# Enclosure_100x68_PBC-AW2.net
KiCad netlist of a schematic drawn in EAGLE
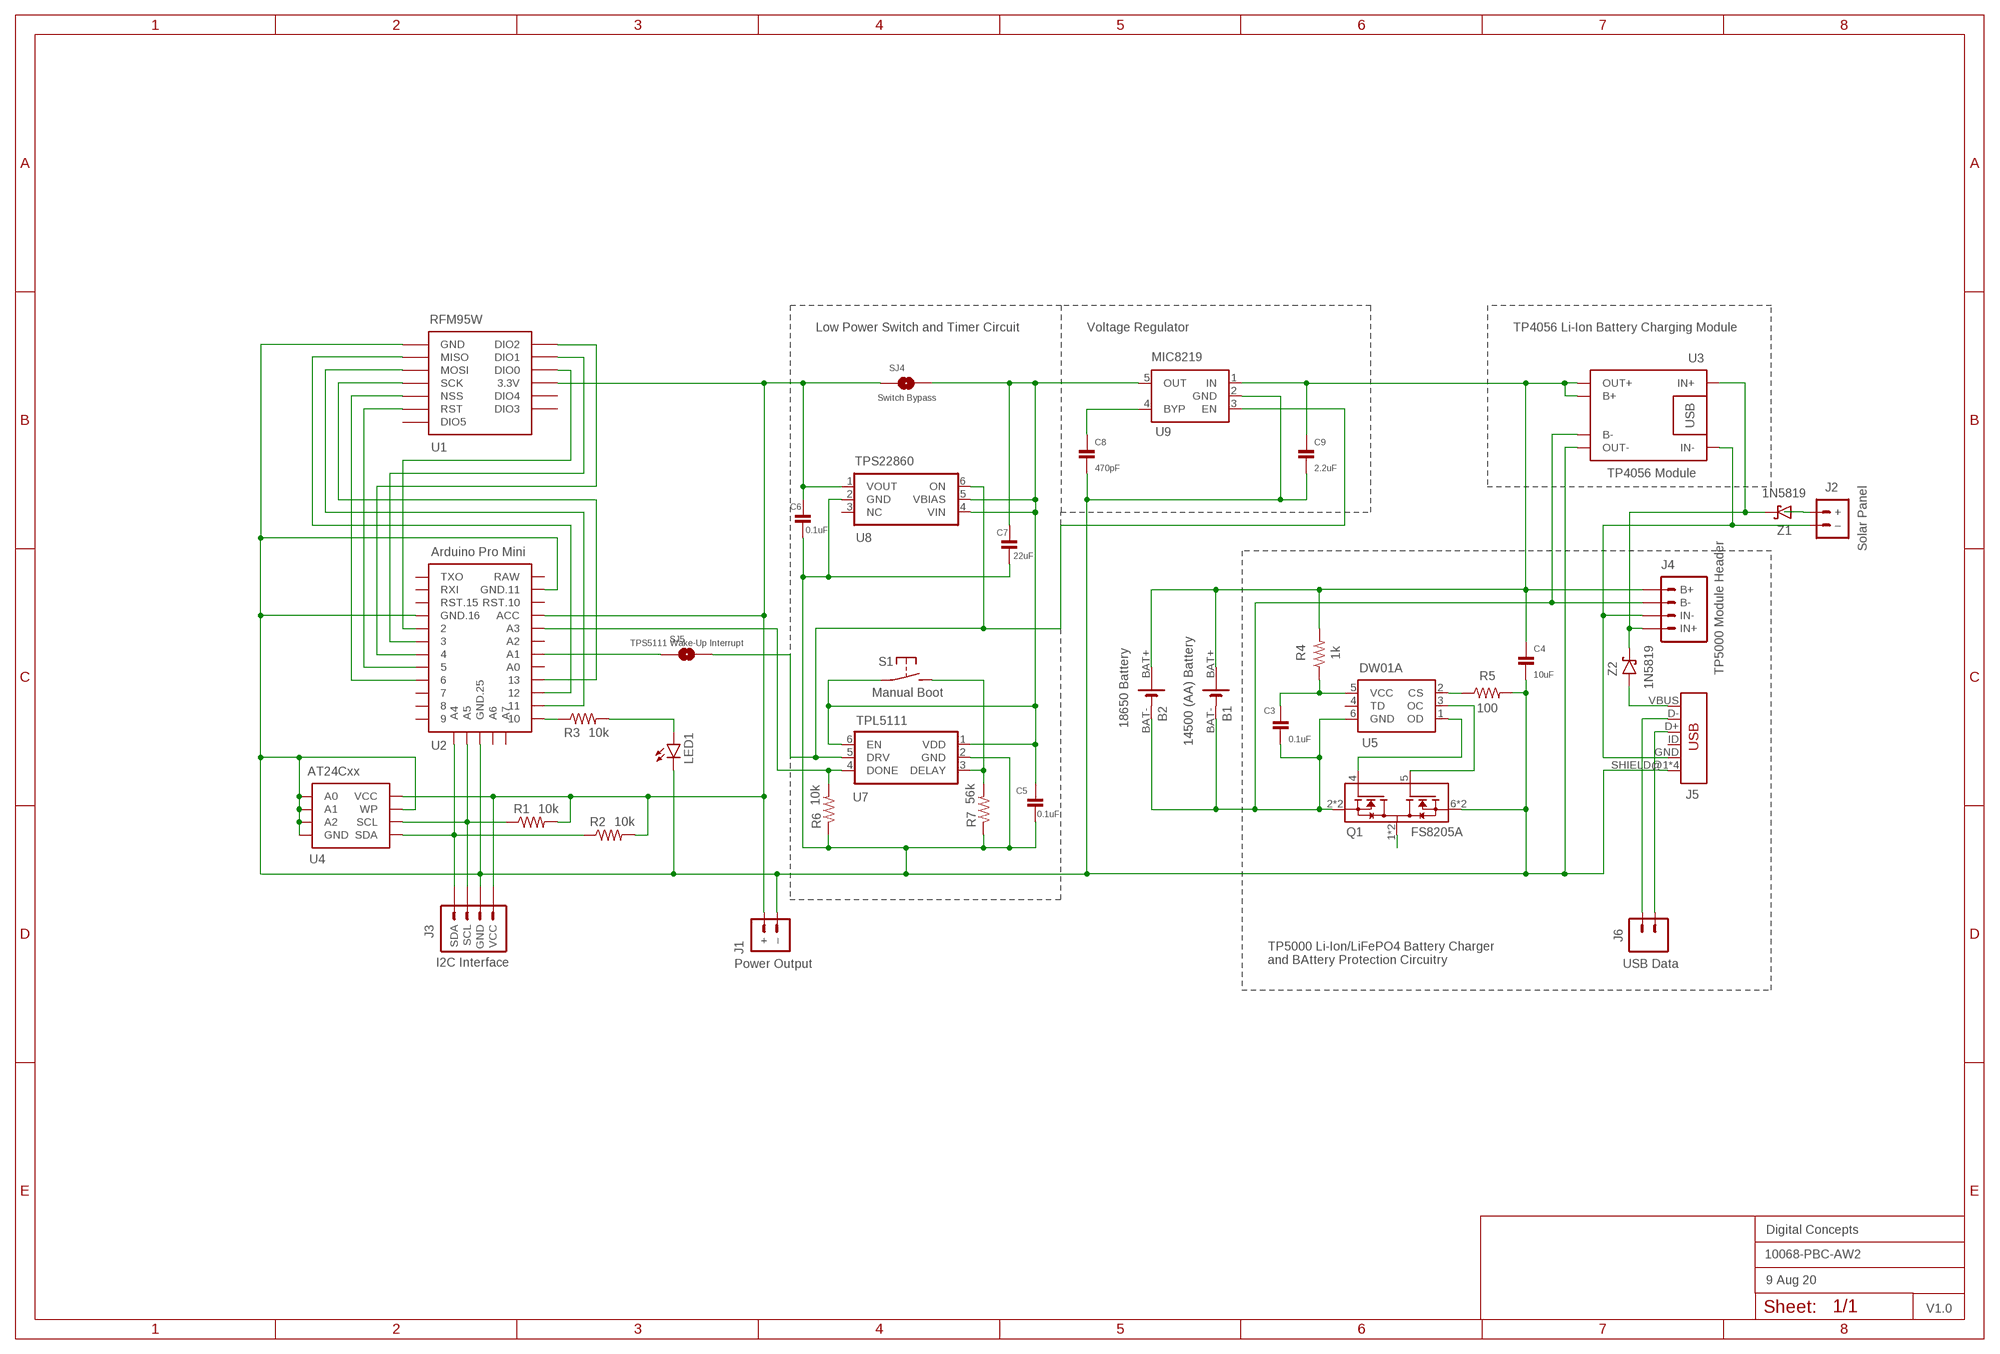
[diagram p0: schematic, sheet 1]

(export (version "E")
  (design (tool "Eeschema 10.0.6"))
  (components
    (comp (ref "B1")
      (value "14500 (AA) Battery")
      (footprint "eagle-import:BATTERY-14500")
      (libsource (lib "eagle-import") (part "BATTERY-HOLDER-14500(AA)"))
    )
    (comp (ref "B2")
      (value "18650 Battery")
      (footprint "eagle-import:BATTERY-18650")
      (libsource (lib "eagle-import") (part "BATTERY-HOLDER-18650"))
    )
    (comp (ref "C3")
      (value "0.1uF")
      (footprint "eagle-import:C0805")
      (libsource (lib "eagle-import") (part "CAPACITOR"))
    )
    (comp (ref "C4")
      (value "10uF")
      (footprint "eagle-import:C0805")
      (libsource (lib "eagle-import") (part "CAPACITOR"))
    )
    (comp (ref "C5")
      (value "0.1uF")
      (footprint "eagle-import:C0805")
      (libsource (lib "eagle-import") (part "CAPACITOR"))
    )
    (comp (ref "C6")
      (value "0.1uF")
      (footprint "eagle-import:C0805")
      (libsource (lib "eagle-import") (part "CAPACITOR"))
    )
    (comp (ref "C7")
      (value "22uF")
      (footprint "eagle-import:C0805")
      (libsource (lib "eagle-import") (part "CAPACITOR"))
    )
    (comp (ref "C8")
      (value "470pF")
      (footprint "eagle-import:C0805")
      (libsource (lib "eagle-import") (part "CAPACITOR"))
    )
    (comp (ref "C9")
      (value "2.2uF")
      (footprint "eagle-import:C0805")
      (libsource (lib "eagle-import") (part "CAPACITOR"))
    )
    (comp (ref "J1")
      (value "Power Output")
      (footprint "eagle-import:JST-PH1.25")
      (libsource (lib "eagle-import") (part "JST-PH1.25-MALE"))
    )
    (comp (ref "J2")
      (value "Solar Panel")
      (footprint "eagle-import:JST-PH2.0")
      (libsource (lib "eagle-import") (part "JST-PH2.0-MALE"))
    )
    (comp (ref "J3")
      (value "I2C Interface")
      (footprint "eagle-import:CONN_04-GENERIC")
      (libsource (lib "eagle-import") (part "I2C-PIN-HEADER"))
    )
    (comp (ref "J4")
      (value "TP5000 Module Header")
      (footprint "eagle-import:CONN_04-GENERIC")
      (libsource (lib "eagle-import") (part "TP5000-MODULE"))
    )
    (comp (ref "J5")
      (value "USB")
      (footprint "eagle-import:USB-MINIB")
      (libsource (lib "eagle-import") (part "USB_MINI-B_SMT"))
    )
    (comp (ref "J6")
      (value "USB Data")
      (footprint "eagle-import:CONN_02-GENERIC")
      (libsource (lib "eagle-import") (part "1X2-PIN-HEADER"))
    )
    (comp (ref "LED1")
      (value "LEDCHIP-LED0805")
      (footprint "eagle-import:CHIP-LED0805")
      (libsource (lib "eagle-import") (part "LEDCHIP-LED0805"))
    )
    (comp (ref "Q1")
      (value "FS8205A")
      (footprint "eagle-import:SOP65P640X120-8N")
      (fields (field (name "MF") "Fortune Semiconductor"))
      (libsource (lib "eagle-import") (part "FS8205A"))
    )
    (comp (ref "R1")
      (value "10k")
      (footprint "eagle-import:R0805")
      (libsource (lib "eagle-import") (part "RESISTORR0805"))
    )
    (comp (ref "R2")
      (value "10k")
      (footprint "eagle-import:R0805")
      (libsource (lib "eagle-import") (part "RESISTORR0805"))
    )
    (comp (ref "R3")
      (value "10k")
      (footprint "eagle-import:R0805")
      (libsource (lib "eagle-import") (part "RESISTORR0805"))
    )
    (comp (ref "R4")
      (value "1k")
      (footprint "eagle-import:R0805")
      (libsource (lib "eagle-import") (part "RESISTORR0805"))
    )
    (comp (ref "R5")
      (value "100")
      (footprint "eagle-import:R0805")
      (libsource (lib "eagle-import") (part "RESISTORR0805"))
    )
    (comp (ref "R6")
      (value "10k")
      (footprint "eagle-import:R0805")
      (libsource (lib "eagle-import") (part "RESISTORR0805"))
    )
    (comp (ref "R7")
      (value "56k")
      (footprint "eagle-import:R0805")
      (libsource (lib "eagle-import") (part "RESISTORR0805"))
    )
    (comp (ref "S1")
      (value "Manual Boot")
      (footprint "eagle-import:2-PAD-SWITCH")
      (libsource (lib "eagle-import") (part "2-PIN-MOMENTARY-SWITCH"))
    )
    (comp (ref "SJ4")
      (value "Switch Bypass")
      (footprint "eagle-import:SJ")
      (libsource (lib "eagle-import") (part "SJ"))
    )
    (comp (ref "SJ5")
      (value "TPS5111 Wake-Up Interrupt")
      (footprint "eagle-import:SJ")
      (libsource (lib "eagle-import") (part "SJ"))
    )
    (comp (ref "U1")
      (value "RFM95W")
      (footprint "eagle-import:RFM95W-PI")
      (libsource (lib "eagle-import") (part "RFM95W-PI"))
    )
    (comp (ref "U2")
      (value "Arduino Pro Mini")
      (footprint "eagle-import:PRO-MINI-29")
      (libsource (lib "eagle-import") (part "ARDUINO-PRO-MINI"))
    )
    (comp (ref "U3")
      (value "TP4056 Module")
      (footprint "eagle-import:BATTERY-CHARGER-LI-PROT")
      (libsource (lib "eagle-import") (part "BATTERY-CHARGER-LI-PROT"))
    )
    (comp (ref "U4")
      (value "AT24Cxx")
      (footprint "eagle-import:SOP-8")
      (libsource (lib "eagle-import") (part "AT24CXX-EEPROM"))
    )
    (comp (ref "U5")
      (value "DW01A")
      (footprint "eagle-import:SOT23-6")
      (fields (field (name "MF") "Fortune Semiconductor"))
      (libsource (lib "eagle-import") (part "DW01A"))
    )
    (comp (ref "U7")
      (value "TPL5111")
      (footprint "eagle-import:SOT-23-6")
      (libsource (lib "eagle-import") (part "TPL5111DDCR"))
    )
    (comp (ref "U8")
      (value "TPS22860")
      (footprint "eagle-import:SOT-23-6")
      (libsource (lib "eagle-import") (part "TPS22860"))
    )
    (comp (ref "U9")
      (value "MIC8219")
      (footprint "eagle-import:SOT-23-5")
      (libsource (lib "eagle-import") (part "MIC5219XX"))
    )
    (comp (ref "Z1")
      (value "1N5819")
      (footprint "eagle-import:SOD-123")
      (libsource (lib "eagle-import") (part "1N5819-SOD-123"))
    )
    (comp (ref "Z2")
      (value "1N5819")
      (footprint "eagle-import:SOD-123")
      (libsource (lib "eagle-import") (part "1N5819-SOD-123"))
    )
  )
  (nets
    (net (code "1") (name "/RAW") (class "Default")
      (node (ref "U2") (pin "RAW") (pinfunction "RAW_RAW") (pintype "power_in"))
    )
    (net (code "2") (name "Net-(J1-–)") (class "Default")
      (node (ref "C4") (pin "2") (pinfunction "2_2") (pintype "passive"))
      (node (ref "C5") (pin "2") (pinfunction "2_2") (pintype "passive"))
      (node (ref "C6") (pin "2") (pinfunction "2_2") (pintype "passive"))
      (node (ref "C7") (pin "2") (pinfunction "2_2") (pintype "passive"))
      (node (ref "C8") (pin "2") (pinfunction "2_2") (pintype "passive"))
      (node (ref "C9") (pin "2") (pinfunction "2_2") (pintype "passive"))
      (node (ref "J1") (pin "-") (pinfunction "–_-") (pintype "power_in"))
      (node (ref "J3") (pin "2") (pinfunction "GND_2") (pintype "passive"))
      (node (ref "J5") (pin "SHIELD@1") (pinfunction "SHIELD_SHIELD@1") (pintype "power_in"))
      (node (ref "J5") (pin "SHIELD@2") (pinfunction "SHIELD_SHIELD@2") (pintype "power_in"))
      (node (ref "J5") (pin "SHIELD@3") (pinfunction "SHIELD_SHIELD@3") (pintype "power_in"))
      (node (ref "J5") (pin "SHIELD@4") (pinfunction "SHIELD_SHIELD@4") (pintype "power_in"))
      (node (ref "LED1") (pin "C") (pinfunction "C_C") (pintype "passive"))
      (node (ref "Q1") (pin "6") (pinfunction "S2_6") (pintype "passive"))
      (node (ref "Q1") (pin "7") (pinfunction "S2_7") (pintype "passive"))
      (node (ref "R5") (pin "2") (pinfunction "2_2") (pintype "passive"))
      (node (ref "R6") (pin "1") (pinfunction "1_1") (pintype "passive"))
      (node (ref "R7") (pin "1") (pinfunction "1_1") (pintype "passive"))
      (node (ref "U1") (pin "GND@3") (pinfunction "GND_GND@3") (pintype "power_in"))
      (node (ref "U1") (pin "GND@6") (pinfunction "GND_GND@6") (pintype "power_in"))
      (node (ref "U2") (pin "GND@11") (pinfunction "GND.25_GND@11") (pintype "bidirectional"))
      (node (ref "U2") (pin "GND@16") (pinfunction "GND.16_GND@16") (pintype "power_in"))
      (node (ref "U2") (pin "GND@25") (pinfunction "GND.11_GND@25") (pintype "power_in"))
      (node (ref "U3") (pin "OUT-") (pinfunction "OUT-_OUT-") (pintype "power_in"))
      (node (ref "U4") (pin "P$1") (pinfunction "A0_P$1") (pintype "bidirectional"))
      (node (ref "U4") (pin "P$2") (pinfunction "A1_P$2") (pintype "bidirectional"))
      (node (ref "U4") (pin "P$3") (pinfunction "A2_P$3") (pintype "bidirectional"))
      (node (ref "U4") (pin "P$4") (pinfunction "GND_P$4") (pintype "bidirectional"))
      (node (ref "U4") (pin "P$7") (pinfunction "WP_P$7") (pintype "bidirectional"))
      (node (ref "U7") (pin "2") (pinfunction "GND_2") (pintype "power_in"))
      (node (ref "U8") (pin "2") (pinfunction "GND_2") (pintype "power_in"))
      (node (ref "U9") (pin "2") (pinfunction "GND_2") (pintype "power_in"))
    )
    (net (code "3") (name "Net-(J2-Pad+)") (class "Default")
      (node (ref "J2") (pin "+") (pinfunction "+_+") (pintype "power_in"))
      (node (ref "Z1") (pin "A") (pinfunction "A_A") (pintype "passive"))
    )
    (net (code "4") (name "Net-(J2-–)") (class "Default")
      (node (ref "J2") (pin "-") (pinfunction "–_-") (pintype "power_in"))
      (node (ref "J4") (pin "2") (pinfunction "IN-_2") (pintype "passive"))
      (node (ref "J5") (pin "GND") (pinfunction "GND_GND") (pintype "power_in"))
      (node (ref "U3") (pin "IN-") (pinfunction "IN-_IN-") (pintype "power_in"))
    )
    (net (code "5") (name "Net-(J3-SCL)") (class "Default")
      (node (ref "J3") (pin "3") (pinfunction "SCL_3") (pintype "passive"))
      (node (ref "R1") (pin "1") (pinfunction "1_1") (pintype "passive"))
      (node (ref "U2") (pin "A5") (pinfunction "A5_A5") (pintype "bidirectional"))
      (node (ref "U4") (pin "P$6") (pinfunction "SCL_P$6") (pintype "bidirectional"))
    )
    (net (code "6") (name "Net-(J3-SDA)") (class "Default")
      (node (ref "J3") (pin "4") (pinfunction "SDA_4") (pintype "passive"))
      (node (ref "R2") (pin "1") (pinfunction "1_1") (pintype "passive"))
      (node (ref "U2") (pin "A4") (pinfunction "A4_A4") (pintype "bidirectional"))
      (node (ref "U4") (pin "P$5") (pinfunction "SDA_P$5") (pintype "bidirectional"))
    )
    (net (code "7") (name "Net-(J3-VCC)") (class "Default")
      (node (ref "C6") (pin "1") (pinfunction "1_1") (pintype "passive"))
      (node (ref "J1") (pin "+") (pinfunction "+_+") (pintype "power_in"))
      (node (ref "J3") (pin "1") (pinfunction "VCC_1") (pintype "passive"))
      (node (ref "R1") (pin "2") (pinfunction "2_2") (pintype "passive"))
      (node (ref "R2") (pin "2") (pinfunction "2_2") (pintype "passive"))
      (node (ref "SJ4") (pin "1") (pinfunction "1_1") (pintype "passive"))
      (node (ref "U1") (pin "3V3") (pinfunction "3.3V_3V3") (pintype "power_in"))
      (node (ref "U2") (pin "ACC") (pinfunction "ACC_ACC") (pintype "power_in"))
      (node (ref "U4") (pin "P$8") (pinfunction "VCC_P$8") (pintype "bidirectional"))
      (node (ref "U8") (pin "1") (pinfunction "VOUT_1") (pintype "power_in"))
    )
    (net (code "8") (name "Net-(J4-B+)") (class "Default")
      (node (ref "B1") (pin "BAT+") (pinfunction "BAT+_BAT+") (pintype "power_in"))
      (node (ref "B2") (pin "BAT+") (pinfunction "BAT+_BAT+") (pintype "power_in"))
      (node (ref "C4") (pin "1") (pinfunction "1_1") (pintype "passive"))
      (node (ref "C9") (pin "1") (pinfunction "1_1") (pintype "passive"))
      (node (ref "J4") (pin "4") (pinfunction "B+_4") (pintype "passive"))
      (node (ref "R4") (pin "2") (pinfunction "2_2") (pintype "passive"))
      (node (ref "U3") (pin "B+") (pinfunction "B+_B+") (pintype "power_in"))
      (node (ref "U3") (pin "OUT+") (pinfunction "OUT+_OUT+") (pintype "power_in"))
      (node (ref "U9") (pin "1") (pinfunction "IN_1") (pintype "power_in"))
    )
    (net (code "9") (name "Net-(J4-B-)") (class "Default")
      (node (ref "B1") (pin "BAT-") (pinfunction "BAT-_BAT-") (pintype "power_in"))
      (node (ref "B2") (pin "BAT-") (pinfunction "BAT-_BAT-") (pintype "power_in"))
      (node (ref "C3") (pin "2") (pinfunction "2_2") (pintype "passive"))
      (node (ref "J4") (pin "3") (pinfunction "B-_3") (pintype "passive"))
      (node (ref "Q1") (pin "2") (pinfunction "S1_2") (pintype "passive"))
      (node (ref "Q1") (pin "3") (pinfunction "S1_3") (pintype "passive"))
      (node (ref "U3") (pin "B-") (pinfunction "B-_B-") (pintype "power_in"))
      (node (ref "U5") (pin "6") (pinfunction "GND_6") (pintype "power_in"))
    )
    (net (code "10") (name "Net-(J4-IN+)") (class "Default")
      (node (ref "J4") (pin "1") (pinfunction "IN+_1") (pintype "passive"))
      (node (ref "U3") (pin "IN+") (pinfunction "IN+_IN+") (pintype "power_in"))
      (node (ref "Z1") (pin "C") (pinfunction "C_C") (pintype "passive"))
      (node (ref "Z2") (pin "C") (pinfunction "C_C") (pintype "passive"))
    )
    (net (code "11") (name "Net-(J5-PadD+)") (class "Default")
      (node (ref "J5") (pin "D+") (pinfunction "D+_D+") (pintype "bidirectional"))
      (node (ref "J6") (pin "2") (pinfunction "2_2") (pintype "passive"))
    )
    (net (code "12") (name "Net-(J5-PadD-)") (class "Default")
      (node (ref "J5") (pin "D-") (pinfunction "D-_D-") (pintype "bidirectional"))
      (node (ref "J6") (pin "1") (pinfunction "1_1") (pintype "passive"))
    )
    (net (code "13") (name "Net-(J5-PadVBUS)") (class "Default")
      (node (ref "J5") (pin "VBUS") (pinfunction "VBUS_VBUS") (pintype "power_in"))
      (node (ref "Z2") (pin "A") (pinfunction "A_A") (pintype "passive"))
    )
    (net (code "14") (name "Net-(LED1-PadA)") (class "Default")
      (node (ref "LED1") (pin "A") (pinfunction "A_A") (pintype "passive"))
      (node (ref "R3") (pin "2") (pinfunction "2_2") (pintype "passive"))
    )
    (net (code "15") (name "Net-(Q1-D12-Pad1)") (class "Default")
      (node (ref "Q1") (pin "1") (pinfunction "D12_1") (pintype "passive"))
      (node (ref "Q1") (pin "8") (pinfunction "D12_8") (pintype "passive"))
    )
    (net (code "16") (name "Net-(Q1-G1)") (class "Default")
      (node (ref "Q1") (pin "4") (pinfunction "G1_4") (pintype "passive"))
      (node (ref "U5") (pin "1") (pinfunction "OD_1") (pintype "bidirectional"))
    )
    (net (code "17") (name "Net-(Q1-G2)") (class "Default")
      (node (ref "Q1") (pin "5") (pinfunction "G2_5") (pintype "passive"))
      (node (ref "U5") (pin "3") (pinfunction "OC_3") (pintype "bidirectional"))
    )
    (net (code "18") (name "Net-(R3-Pad1)") (class "Default")
      (node (ref "R3") (pin "1") (pinfunction "1_1") (pintype "passive"))
      (node (ref "U2") (pin "10") (pinfunction "10_10") (pintype "bidirectional"))
    )
    (net (code "19") (name "Net-(S1-P)") (class "Default")
      (node (ref "C5") (pin "1") (pinfunction "1_1") (pintype "passive"))
      (node (ref "C7") (pin "1") (pinfunction "1_1") (pintype "passive"))
      (node (ref "S1") (pin "P$1") (pinfunction "P_P$1") (pintype "passive"))
      (node (ref "SJ4") (pin "2") (pinfunction "2_2") (pintype "passive"))
      (node (ref "U7") (pin "1") (pinfunction "VDD_1") (pintype "power_in"))
      (node (ref "U7") (pin "6") (pinfunction "EN_6") (pintype "input"))
      (node (ref "U8") (pin "4") (pinfunction "VIN_4") (pintype "power_in"))
      (node (ref "U8") (pin "5") (pinfunction "VBIAS_5") (pintype "input"))
      (node (ref "U9") (pin "5") (pinfunction "OUT_5") (pintype "power_in"))
    )
    (net (code "20") (name "Net-(S1-S)") (class "Default")
      (node (ref "R7") (pin "2") (pinfunction "2_2") (pintype "passive"))
      (node (ref "S1") (pin "P$2") (pinfunction "S_P$2") (pintype "passive"))
      (node (ref "U7") (pin "3") (pinfunction "DELAY_3") (pintype "input"))
    )
    (net (code "21") (name "Net-(SJ5-Pad1)") (class "Default")
      (node (ref "SJ5") (pin "1") (pinfunction "1_1") (pintype "passive"))
      (node (ref "U2") (pin "A1") (pinfunction "A1_A1") (pintype "bidirectional"))
    )
    (net (code "22") (name "Net-(U1-PadDIO0)") (class "Default")
      (node (ref "U1") (pin "DIO0") (pinfunction "DIO0_DIO0") (pintype "bidirectional"))
      (node (ref "U2") (pin "2") (pinfunction "2_2") (pintype "bidirectional"))
    )
    (net (code "23") (name "Net-(U1-PadDIO1)") (class "Default")
      (node (ref "U1") (pin "DIO1") (pinfunction "DIO1_DIO1") (pintype "bidirectional"))
      (node (ref "U2") (pin "3") (pinfunction "3_3") (pintype "bidirectional"))
    )
    (net (code "24") (name "Net-(U1-PadDIO2)") (class "Default")
      (node (ref "U1") (pin "DIO2") (pinfunction "DIO2_DIO2") (pintype "bidirectional"))
      (node (ref "U2") (pin "4") (pinfunction "4_4") (pintype "bidirectional"))
    )
    (net (code "25") (name "Net-(U1-PadMISO)") (class "Default")
      (node (ref "U1") (pin "MISO") (pinfunction "MISO_MISO") (pintype "bidirectional"))
      (node (ref "U2") (pin "12") (pinfunction "12_12") (pintype "bidirectional"))
    )
    (net (code "26") (name "Net-(U1-PadMOSI)") (class "Default")
      (node (ref "U1") (pin "MOSI") (pinfunction "MOSI_MOSI") (pintype "bidirectional"))
      (node (ref "U2") (pin "11") (pinfunction "11_11") (pintype "bidirectional"))
    )
    (net (code "27") (name "Net-(U1-PadNSS)") (class "Default")
      (node (ref "U1") (pin "NSS") (pinfunction "NSS_NSS") (pintype "bidirectional"))
      (node (ref "U2") (pin "6") (pinfunction "6_6") (pintype "bidirectional"))
    )
    (net (code "28") (name "Net-(U1-PadRST)") (class "Default")
      (node (ref "U1") (pin "RST") (pinfunction "RST_RST") (pintype "bidirectional"))
      (node (ref "U2") (pin "5") (pinfunction "5_5") (pintype "bidirectional"))
    )
    (net (code "29") (name "Net-(U1-PadSCK)") (class "Default")
      (node (ref "U1") (pin "SCK") (pinfunction "SCK_SCK") (pintype "bidirectional"))
      (node (ref "U2") (pin "13") (pinfunction "13_13") (pintype "bidirectional"))
    )
    (net (code "30") (name "Net-(U5-CS)") (class "Default")
      (node (ref "R5") (pin "1") (pinfunction "1_1") (pintype "passive"))
      (node (ref "U5") (pin "2") (pinfunction "CS_2") (pintype "bidirectional"))
    )
    (net (code "31") (name "Net-(U5-VCC)") (class "Default")
      (node (ref "C3") (pin "1") (pinfunction "1_1") (pintype "passive"))
      (node (ref "R4") (pin "1") (pinfunction "1_1") (pintype "passive"))
      (node (ref "U5") (pin "5") (pinfunction "VCC_5") (pintype "power_in"))
    )
    (net (code "32") (name "Net-(U7-DONE)") (class "Default")
      (node (ref "R6") (pin "2") (pinfunction "2_2") (pintype "passive"))
      (node (ref "U2") (pin "A3") (pinfunction "A3_A3") (pintype "bidirectional"))
      (node (ref "U7") (pin "4") (pinfunction "DONE_4") (pintype "input"))
    )
    (net (code "33") (name "Net-(U7-DRV)") (class "Default")
      (node (ref "SJ5") (pin "2") (pinfunction "2_2") (pintype "passive"))
      (node (ref "U7") (pin "5") (pinfunction "DRV_5") (pintype "output"))
      (node (ref "U8") (pin "6") (pinfunction "ON_6") (pintype "input"))
      (node (ref "U9") (pin "3") (pinfunction "EN_3") (pintype "input"))
    )
    (net (code "34") (name "Net-(U9-BYP)") (class "Default")
      (node (ref "C8") (pin "1") (pinfunction "1_1") (pintype "passive"))
      (node (ref "U9") (pin "4") (pinfunction "BYP_4") (pintype "passive"))
    )
    (net (code "35") (name "unconnected-(J5-PadID)") (class "Default")
      (node (ref "J5") (pin "ID") (pinfunction "ID_ID") (pintype "bidirectional"))
    )
    (net (code "36") (name "unconnected-(U1-PadDIO3)") (class "Default")
      (node (ref "U1") (pin "DIO3") (pinfunction "DIO3_DIO3") (pintype "bidirectional"))
    )
    (net (code "37") (name "unconnected-(U1-PadDIO4)") (class "Default")
      (node (ref "U1") (pin "DIO4") (pinfunction "DIO4_DIO4") (pintype "bidirectional"))
    )
    (net (code "38") (name "unconnected-(U1-PadDIO5)") (class "Default")
      (node (ref "U1") (pin "DIO5") (pinfunction "DIO5_DIO5") (pintype "bidirectional"))
    )
    (net (code "39") (name "unconnected-(U2-Pad7)") (class "Default")
      (node (ref "U2") (pin "7") (pinfunction "7_7") (pintype "bidirectional"))
    )
    (net (code "40") (name "unconnected-(U2-Pad8)") (class "Default")
      (node (ref "U2") (pin "8") (pinfunction "8_8") (pintype "bidirectional"))
    )
    (net (code "41") (name "unconnected-(U2-Pad9)") (class "Default")
      (node (ref "U2") (pin "9") (pinfunction "9_9") (pintype "bidirectional"))
    )
    (net (code "42") (name "unconnected-(U2-PadA0)") (class "Default")
      (node (ref "U2") (pin "A0") (pinfunction "A0_A0") (pintype "bidirectional"))
    )
    (net (code "43") (name "unconnected-(U2-PadA2)") (class "Default")
      (node (ref "U2") (pin "A2") (pinfunction "A2_A2") (pintype "bidirectional"))
    )
    (net (code "44") (name "unconnected-(U2-PadA6)") (class "Default")
      (node (ref "U2") (pin "A6") (pinfunction "A6_A6") (pintype "bidirectional"))
    )
    (net (code "45") (name "unconnected-(U2-PadA7)") (class "Default")
      (node (ref "U2") (pin "A7") (pinfunction "A7_A7") (pintype "bidirectional"))
    )
    (net (code "46") (name "unconnected-(U2-PadRXI)") (class "Default")
      (node (ref "U2") (pin "RXI") (pinfunction "RXI_RXI") (pintype "input"))
    )
    (net (code "47") (name "unconnected-(U2-PadTXO)") (class "Default")
      (node (ref "U2") (pin "TXO") (pinfunction "TXO_TXO") (pintype "bidirectional"))
    )
    (net (code "48") (name "unconnected-(U2-RST.10-PadRST@10)") (class "Default")
      (node (ref "U2") (pin "RST@10") (pinfunction "RST.10_RST@10") (pintype "input"))
    )
    (net (code "49") (name "unconnected-(U2-RST.15-PadRST@15)") (class "Default")
      (node (ref "U2") (pin "RST@15") (pinfunction "RST.15_RST@15") (pintype "input"))
    )
    (net (code "50") (name "unconnected-(U5-TD-Pad4)") (class "Default")
      (node (ref "U5") (pin "4") (pinfunction "TD_4") (pintype "bidirectional"))
    )
    (net (code "51") (name "unconnected-(U8-NC-Pad3)") (class "Default")
      (node (ref "U8") (pin "3") (pinfunction "NC_3") (pintype "no_connect"))
    )
  )
)
